# POWER_SUPPLY.net
KiCad netlist of a schematic drawn in Altium Designer
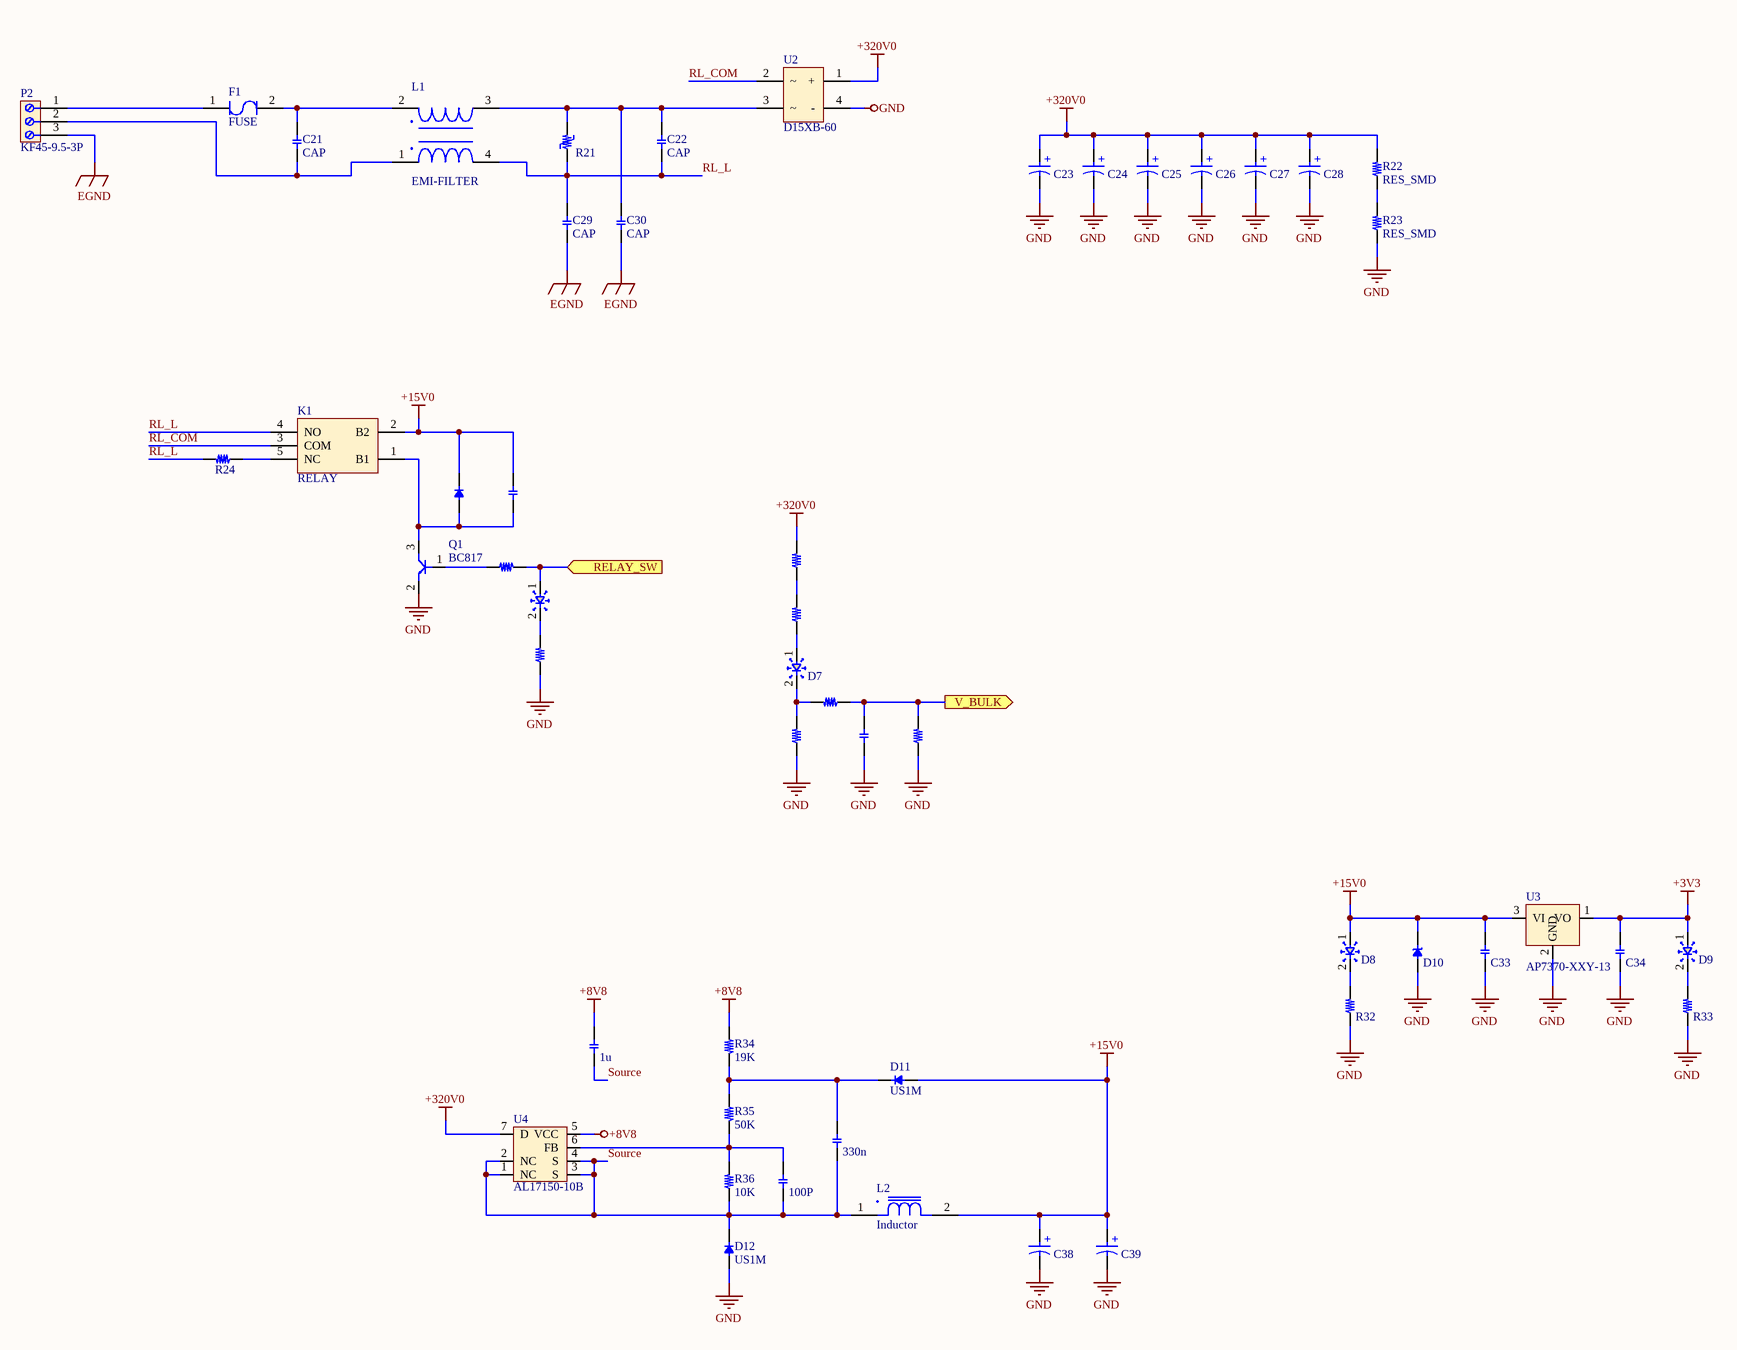
[diagram p0: POWER_SUPPLY.SchDoc]

(export (version "E")
  (design (tool "Eeschema 10.0.6"))
  (components
    (comp (ref "C21")
      (value "CAP")
      (footprint "C FILM 15mm")
      (libsource (lib "radmehr_library") (part "CAP"))
    )
    (comp (ref "C22")
      (value "CAP")
      (footprint "C FILM 15mm")
      (libsource (lib "radmehr_library") (part "CAP"))
    )
    (comp (ref "C23")
      (value "220µF")
      (footprint "WCAP-AIG8_D25H30")
      (description "WCAP-AIG8 Aluminum Electrolytic Capacitor, Snap-In, D25 x H30mm, 220µF, 400V")
      (fields
        (field (name "MANUFACTURER PART NUMBER") "861011384014")
        (field (name "MANUFACTURER") "Wurth Elektronik")
      )
      (libsource (lib "Altium_WCAP-AIG8 (rev22c)") (part "861011384014"))
    )
    (comp (ref "C24")
      (value "220µF")
      (footprint "WCAP-AIG8_D25H30")
      (description "WCAP-AIG8 Aluminum Electrolytic Capacitor, Snap-In, D25 x H30mm, 220µF, 400V")
      (fields
        (field (name "MANUFACTURER PART NUMBER") "861011384014")
        (field (name "MANUFACTURER") "Wurth Elektronik")
      )
      (libsource (lib "Altium_WCAP-AIG8 (rev22c)") (part "861011384014"))
    )
    (comp (ref "C25")
      (value "220µF")
      (footprint "WCAP-AIG8_D25H30")
      (description "WCAP-AIG8 Aluminum Electrolytic Capacitor, Snap-In, D25 x H30mm, 220µF, 400V")
      (fields
        (field (name "MANUFACTURER PART NUMBER") "861011384014")
        (field (name "MANUFACTURER") "Wurth Elektronik")
      )
      (libsource (lib "Altium_WCAP-AIG8 (rev22c)") (part "861011384014"))
    )
    (comp (ref "C26")
      (value "220µF")
      (footprint "WCAP-AIG8_D25H30")
      (description "WCAP-AIG8 Aluminum Electrolytic Capacitor, Snap-In, D25 x H30mm, 220µF, 400V")
      (fields
        (field (name "MANUFACTURER PART NUMBER") "861011384014")
        (field (name "MANUFACTURER") "Wurth Elektronik")
      )
      (libsource (lib "Altium_WCAP-AIG8 (rev22c)") (part "861011384014"))
    )
    (comp (ref "C27")
      (value "220µF")
      (footprint "WCAP-AIG8_D25H30")
      (description "WCAP-AIG8 Aluminum Electrolytic Capacitor, Snap-In, D25 x H30mm, 220µF, 400V")
      (fields
        (field (name "MANUFACTURER PART NUMBER") "861011384014")
        (field (name "MANUFACTURER") "Wurth Elektronik")
      )
      (libsource (lib "Altium_WCAP-AIG8 (rev22c)") (part "861011384014"))
    )
    (comp (ref "C28")
      (value "220µF")
      (footprint "WCAP-AIG8_D25H30")
      (description "WCAP-AIG8 Aluminum Electrolytic Capacitor, Snap-In, D25 x H30mm, 220µF, 400V")
      (fields
        (field (name "MANUFACTURER PART NUMBER") "861011384014")
        (field (name "MANUFACTURER") "Wurth Elektronik")
      )
      (libsource (lib "Altium_WCAP-AIG8 (rev22c)") (part "861011384014"))
    )
    (comp (ref "C29") (value "CAP") (footprint "CXY") (libsource (lib "radmehr_library") (part "CAP")))
    (comp (ref "C30") (value "CAP") (footprint "CXY") (libsource (lib "radmehr_library") (part "CAP")))
    (comp (ref "C31")
      (value "CAP_SMD")
      (footprint "C 0603")
      (libsource (lib "radmehr_library") (part "CAP_SMD"))
    )
    (comp (ref "C32")
      (value "CAP_SMD")
      (footprint "C 1206")
      (libsource (lib "radmehr_library") (part "CAP_SMD"))
    )
    (comp (ref "C33")
      (value "CAP_SMD")
      (footprint "C 0603")
      (libsource (lib "radmehr_library") (part "CAP_SMD"))
    )
    (comp (ref "C34")
      (value "CAP_SMD")
      (footprint "C 0603")
      (libsource (lib "radmehr_library") (part "CAP_SMD"))
    )
    (comp (ref "C35")
      (value "1u")
      (footprint "C 1206")
      (description "CAP_SMD")
      (libsource (lib "radmehr_library") (part "CAP_SMD"))
    )
    (comp (ref "C36")
      (value "330n")
      (footprint "C 1206")
      (description "CAP_SMD")
      (libsource (lib "radmehr_library") (part "CAP_SMD"))
    )
    (comp (ref "C37")
      (value "100P")
      (footprint "C 1206")
      (description "CAP_SMD")
      (libsource (lib "radmehr_library") (part "CAP_SMD"))
    )
    (comp (ref "C38")
      (value "220uF")
      (footprint "WCAP-ASLI_D10H10.5")
      (description "WCAP-ASLI Aluminum Electrolytic Capacitor, V-Chip, D10 x H10.5mm, 220uF, 50V")
      (fields
        (field (name "MANUFACTURER PART NUMBER") "865080657018")
        (field (name "MANUFACTURER") "Wurth Elektronik")
      )
      (libsource (lib "Altium_WCAP-ASLI (rev22d)") (part "865080657018"))
    )
    (comp (ref "C39")
      (value "220uF")
      (footprint "WCAP-ASLI_D10H10.5")
      (description "WCAP-ASLI Aluminum Electrolytic Capacitor, V-Chip, D10 x H10.5mm, 220uF, 50V")
      (fields
        (field (name "MANUFACTURER PART NUMBER") "865080657018")
        (field (name "MANUFACTURER") "Wurth Elektronik")
      )
      (libsource (lib "Altium_WCAP-ASLI (rev22d)") (part "865080657018"))
    )
    (comp (ref "D5")
      (value "DIOD_SMD")
      (footprint "D SOD-323")
      (libsource (lib "radmehr_library") (part "DIOD_SMD"))
    )
    (comp (ref "D6")
      (value "LED_SMD")
      (footprint "D 0603")
      (libsource (lib "radmehr_library") (part "LED_SMD"))
    )
    (comp (ref "D7")
      (value "LED_SMD")
      (footprint "D 1206")
      (libsource (lib "radmehr_library") (part "LED_SMD"))
    )
    (comp (ref "D8")
      (value "LED_SMD")
      (footprint "D 0603")
      (libsource (lib "radmehr_library") (part "LED_SMD"))
    )
    (comp (ref "D9")
      (value "LED_SMD")
      (footprint "D 0603")
      (libsource (lib "radmehr_library") (part "LED_SMD"))
    )
    (comp (ref "D10")
      (value "TVS_UI")
      (footprint "D SOD-123")
      (libsource (lib "radmehr_library") (part "DIOD_SMD_TVS_UI"))
    )
    (comp (ref "D11")
      (value "US1M")
      (footprint "DIOD_SMA")
      (description "DIOD_SMD")
      (libsource (lib "radmehr_library") (part "DIOD_SMD"))
    )
    (comp (ref "D12")
      (value "US1M")
      (footprint "DIOD_SMA")
      (description "DIOD_SMD")
      (libsource (lib "radmehr_library") (part "DIOD_SMD"))
    )
    (comp (ref "F1") (value "FUSE") (footprint "FUSE 1") (libsource (lib "radmehr_library") (part "FUSE")))
    (comp (ref "K1") (value "RELAY") (footprint "ALQ124") (libsource (lib "radmehr_library") (part "RELAY")))
    (comp (ref "L1")
      (value "EMI-FILTER")
      (footprint "EMI-FILTER-10*13")
      (libsource (lib "radmehr_library") (part "EMI-FILTER"))
    )
    (comp (ref "L2")
      (value "Inductor")
      (footprint "L_10*10_SMD")
      (libsource (lib "radmehr_library") (part "Inductor"))
    )
    (comp (ref "P2")
      (value "KF45-9.5-3P")
      (footprint "DG45C-B-03P-13")
      (libsource (lib "TERMINAL") (part "KF45-9.5-3P"))
    )
    (comp (ref "Q1")
      (value "BC817")
      (footprint "SOT-23_3_Q")
      (libsource (lib "radmehr_library") (part "BC817"))
    )
    (comp (ref "R21")
      (value "VARISTOR")
      (footprint "RTD")
      (libsource (lib "radmehr_library") (part "VARISTOR"))
    )
    (comp (ref "R22")
      (value "RES_SMD")
      (footprint "R 2512")
      (libsource (lib "radmehr_library") (part "RES_SMD"))
    )
    (comp (ref "R23")
      (value "RES_SMD")
      (footprint "R 2512")
      (libsource (lib "radmehr_library") (part "RES_SMD"))
    )
    (comp (ref "R24")
      (value "RES_THD")
      (footprint "R 5W VER")
      (libsource (lib "radmehr_library") (part "RES_THD"))
    )
    (comp (ref "R25")
      (value "RES_SMD")
      (footprint "R 1206")
      (libsource (lib "radmehr_library") (part "RES_SMD"))
    )
    (comp (ref "R26")
      (value "RES_SMD")
      (footprint "R 0603")
      (libsource (lib "radmehr_library") (part "RES_SMD"))
    )
    (comp (ref "R27")
      (value "RES_SMD")
      (footprint "R 1206")
      (libsource (lib "radmehr_library") (part "RES_SMD"))
    )
    (comp (ref "R28")
      (value "RES_SMD")
      (footprint "R 0603")
      (libsource (lib "radmehr_library") (part "RES_SMD"))
    )
    (comp (ref "R29")
      (value "RES_SMD")
      (footprint "R 1206")
      (libsource (lib "radmehr_library") (part "RES_SMD"))
    )
    (comp (ref "R30")
      (value "RES_SMD")
      (footprint "R 1206")
      (libsource (lib "radmehr_library") (part "RES_SMD"))
    )
    (comp (ref "R31")
      (value "RES_SMD")
      (footprint "R 0603")
      (libsource (lib "radmehr_library") (part "RES_SMD"))
    )
    (comp (ref "R32")
      (value "RES_SMD")
      (footprint "R 0603")
      (libsource (lib "radmehr_library") (part "RES_SMD"))
    )
    (comp (ref "R33")
      (value "RES_SMD")
      (footprint "R 0603")
      (libsource (lib "radmehr_library") (part "RES_SMD"))
    )
    (comp (ref "R34")
      (value "19K")
      (footprint "R 1206")
      (description "RES_SMD")
      (libsource (lib "radmehr_library") (part "RES_SMD"))
    )
    (comp (ref "R35")
      (value "50K")
      (footprint "R 1206")
      (description "RES_SMD")
      (libsource (lib "radmehr_library") (part "RES_SMD"))
    )
    (comp (ref "R36")
      (value "10K")
      (footprint "R 1206")
      (description "RES_SMD")
      (libsource (lib "radmehr_library") (part "RES_SMD"))
    )
    (comp (ref "U2")
      (value "D15XB-60")
      (footprint "D15XB-60")
      (libsource (lib "radmehr_library") (part "D15XB-60"))
    )
    (comp (ref "U3")
      (value "AP7370-XXY-13")
      (footprint "SOT89-U")
      (libsource (lib "radmehr_library") (part "AP7370-XXY-13"))
    )
    (comp (ref "U4")
      (value "AL17150-10B")
      (footprint "SOIC-7")
      (libsource (lib "radmehr_library") (part "AL17150-10B"))
    )
  )
  (nets
    (net (code "1") (name "+3V3") (class "Default")
      (node (ref "C34") (pin "2") (pinfunction "2_2") (pintype "passive"))
      (node (ref "D9") (pin "1") (pintype "passive"))
      (node (ref "U3") (pin "1") (pinfunction "VO_1") (pintype "passive"))
    )
    (net (code "2") (name "+8V8") (class "Default")
      (node (ref "C35") (pin "2") (pinfunction "2_2") (pintype "passive"))
      (node (ref "R34") (pin "1") (pinfunction "1_1") (pintype "passive"))
      (node (ref "U4") (pin "5") (pinfunction "VCC_5") (pintype "passive"))
    )
    (net (code "3") (name "+15V0") (class "Default")
      (node (ref "C31") (pin "2") (pinfunction "2_2") (pintype "passive"))
      (node (ref "C33") (pin "2") (pinfunction "2_2") (pintype "passive"))
      (node (ref "C38") (pin "1") (pinfunction "P_1") (pintype "passive"))
      (node (ref "C39") (pin "1") (pinfunction "P_1") (pintype "passive"))
      (node (ref "D10") (pin "2") (pinfunction "2_2") (pintype "passive"))
      (node (ref "D11") (pin "1") (pinfunction "1_1") (pintype "passive"))
      (node (ref "D5") (pin "2") (pinfunction "2_2") (pintype "passive"))
      (node (ref "D8") (pin "1") (pintype "passive"))
      (node (ref "K1") (pin "2") (pinfunction "B2_2") (pintype "power_in"))
      (node (ref "L2") (pin "2") (pintype "passive"))
      (node (ref "U3") (pin "3") (pinfunction "VI_3") (pintype "passive"))
    )
    (net (code "4") (name "+320V0") (class "Default")
      (node (ref "C23") (pin "1") (pinfunction "P_1") (pintype "passive"))
      (node (ref "C24") (pin "1") (pinfunction "P_1") (pintype "passive"))
      (node (ref "C25") (pin "1") (pinfunction "P_1") (pintype "passive"))
      (node (ref "C26") (pin "1") (pinfunction "P_1") (pintype "passive"))
      (node (ref "C27") (pin "1") (pinfunction "P_1") (pintype "passive"))
      (node (ref "C28") (pin "1") (pinfunction "P_1") (pintype "passive"))
      (node (ref "R22") (pin "2") (pinfunction "2_2") (pintype "passive"))
      (node (ref "R25") (pin "2") (pinfunction "2_2") (pintype "passive"))
      (node (ref "U2") (pin "1") (pinfunction "+_1") (pintype "passive"))
      (node (ref "U4") (pin "7") (pinfunction "D_7") (pintype "passive"))
    )
    (net (code "5") (name "/RELAY_SW") (class "Default")
      (node (ref "D6") (pin "1") (pintype "passive"))
      (node (ref "R26") (pin "2") (pinfunction "2_2") (pintype "passive"))
    )
    (net (code "6") (name "/RL_COM") (class "Default")
      (node (ref "K1") (pin "3") (pinfunction "COM_3") (pintype "power_in"))
      (node (ref "U2") (pin "2") (pinfunction "~_2") (pintype "passive"))
    )
    (net (code "7") (name "/RL_L") (class "Default")
      (node (ref "C22") (pin "1") (pinfunction "1_1") (pintype "passive"))
      (node (ref "C29") (pin "2") (pinfunction "2_2") (pintype "passive"))
      (node (ref "K1") (pin "4") (pinfunction "NO_4") (pintype "power_in"))
      (node (ref "L1") (pin "4") (pinfunction "4_4") (pintype "power_in"))
      (node (ref "R21") (pin "1") (pinfunction "1_1") (pintype "passive"))
      (node (ref "R24") (pin "2") (pinfunction "2_2") (pintype "passive"))
    )
    (net (code "8") (name "/Source") (class "Default")
      (node (ref "C35") (pin "1") (pinfunction "1_1") (pintype "passive"))
      (node (ref "C36") (pin "1") (pinfunction "1_1") (pintype "passive"))
      (node (ref "C37") (pin "1") (pinfunction "1_1") (pintype "passive"))
      (node (ref "D12") (pin "2") (pinfunction "2_2") (pintype "passive"))
      (node (ref "L2") (pin "1") (pintype "passive"))
      (node (ref "R36") (pin "1") (pinfunction "1_1") (pintype "passive"))
      (node (ref "U4") (pin "1") (pinfunction "NC_1") (pintype "passive"))
      (node (ref "U4") (pin "2") (pinfunction "NC_2") (pintype "passive"))
      (node (ref "U4") (pin "3") (pinfunction "S_3") (pintype "passive"))
      (node (ref "U4") (pin "4") (pinfunction "S_4") (pintype "passive"))
    )
    (net (code "9") (name "/V_BULK") (class "Default")
      (node (ref "C32") (pin "2") (pinfunction "2_2") (pintype "passive"))
      (node (ref "R29") (pin "1") (pinfunction "1_1") (pintype "passive"))
      (node (ref "R31") (pin "2") (pinfunction "2_2") (pintype "passive"))
    )
    (net (code "10") (name "EGND") (class "Default")
      (node (ref "C29") (pin "1") (pinfunction "1_1") (pintype "passive"))
      (node (ref "C30") (pin "1") (pinfunction "1_1") (pintype "passive"))
      (node (ref "P2") (pin "3") (pinfunction "3_3") (pintype "passive"))
    )
    (net (code "11") (name "GND") (class "Default")
      (node (ref "C23") (pin "2") (pinfunction "N_2") (pintype "passive"))
      (node (ref "C24") (pin "2") (pinfunction "N_2") (pintype "passive"))
      (node (ref "C25") (pin "2") (pinfunction "N_2") (pintype "passive"))
      (node (ref "C26") (pin "2") (pinfunction "N_2") (pintype "passive"))
      (node (ref "C27") (pin "2") (pinfunction "N_2") (pintype "passive"))
      (node (ref "C28") (pin "2") (pinfunction "N_2") (pintype "passive"))
      (node (ref "C32") (pin "1") (pinfunction "1_1") (pintype "passive"))
      (node (ref "C33") (pin "1") (pinfunction "1_1") (pintype "passive"))
      (node (ref "C34") (pin "1") (pinfunction "1_1") (pintype "passive"))
      (node (ref "C38") (pin "2") (pinfunction "N_2") (pintype "passive"))
      (node (ref "C39") (pin "2") (pinfunction "N_2") (pintype "passive"))
      (node (ref "D10") (pin "1") (pinfunction "1_1") (pintype "passive"))
      (node (ref "D12") (pin "1") (pinfunction "1_1") (pintype "passive"))
      (node (ref "Q1") (pin "2") (pinfunction "E_2") (pintype "passive"))
      (node (ref "R23") (pin "1") (pinfunction "1_1") (pintype "passive"))
      (node (ref "R28") (pin "1") (pinfunction "1_1") (pintype "passive"))
      (node (ref "R30") (pin "1") (pinfunction "1_1") (pintype "passive"))
      (node (ref "R31") (pin "1") (pinfunction "1_1") (pintype "passive"))
      (node (ref "R32") (pin "1") (pinfunction "1_1") (pintype "passive"))
      (node (ref "R33") (pin "1") (pinfunction "1_1") (pintype "passive"))
      (node (ref "U2") (pin "4") (pinfunction "-_4") (pintype "passive"))
      (node (ref "U3") (pin "2") (pinfunction "GND_2") (pintype "passive"))
    )
    (net (code "12") (name "Net-(C21-Pad1)") (class "Default")
      (node (ref "C21") (pin "1") (pinfunction "1_1") (pintype "passive"))
      (node (ref "L1") (pin "1") (pinfunction "1_1") (pintype "power_in"))
      (node (ref "P2") (pin "2") (pinfunction "2_2") (pintype "passive"))
    )
    (net (code "13") (name "Net-(C21-Pad2)") (class "Default")
      (node (ref "C21") (pin "2") (pinfunction "2_2") (pintype "passive"))
      (node (ref "F1") (pin "2") (pintype "passive"))
      (node (ref "L1") (pin "2") (pinfunction "2_2") (pintype "power_in"))
    )
    (net (code "14") (name "Net-(C22-Pad2)") (class "Default")
      (node (ref "C22") (pin "2") (pinfunction "2_2") (pintype "passive"))
      (node (ref "C30") (pin "2") (pinfunction "2_2") (pintype "passive"))
      (node (ref "L1") (pin "3") (pinfunction "3_3") (pintype "power_in"))
      (node (ref "R21") (pin "2") (pinfunction "2_2") (pintype "passive"))
      (node (ref "U2") (pin "3") (pinfunction "~_3") (pintype "passive"))
    )
    (net (code "15") (name "Net-(C36-Pad2)") (class "Default")
      (node (ref "C36") (pin "2") (pinfunction "2_2") (pintype "passive"))
      (node (ref "D11") (pin "2") (pinfunction "2_2") (pintype "passive"))
      (node (ref "R34") (pin "2") (pinfunction "2_2") (pintype "passive"))
      (node (ref "R35") (pin "1") (pinfunction "1_1") (pintype "passive"))
    )
    (net (code "16") (name "Net-(D6-Pad2)") (class "Default")
      (node (ref "D6") (pin "2") (pintype "passive"))
      (node (ref "R28") (pin "2") (pinfunction "2_2") (pintype "passive"))
    )
    (net (code "17") (name "Net-(D7-Pad1)") (class "Default")
      (node (ref "D7") (pin "1") (pintype "passive"))
      (node (ref "R27") (pin "1") (pinfunction "1_1") (pintype "passive"))
    )
    (net (code "18") (name "Net-(D7-Pad2)") (class "Default")
      (node (ref "D7") (pin "2") (pintype "passive"))
      (node (ref "R29") (pin "2") (pinfunction "2_2") (pintype "passive"))
      (node (ref "R30") (pin "2") (pinfunction "2_2") (pintype "passive"))
    )
    (net (code "19") (name "Net-(D8-Pad2)") (class "Default")
      (node (ref "D8") (pin "2") (pintype "passive"))
      (node (ref "R32") (pin "2") (pinfunction "2_2") (pintype "passive"))
    )
    (net (code "20") (name "Net-(D9-Pad2)") (class "Default")
      (node (ref "D9") (pin "2") (pintype "passive"))
      (node (ref "R33") (pin "2") (pinfunction "2_2") (pintype "passive"))
    )
    (net (code "21") (name "Net-(F1-Pad1)") (class "Default")
      (node (ref "F1") (pin "1") (pintype "passive"))
      (node (ref "P2") (pin "1") (pinfunction "1_1") (pintype "passive"))
    )
    (net (code "22") (name "Net-(K1-B1)") (class "Default")
      (node (ref "C31") (pin "1") (pinfunction "1_1") (pintype "passive"))
      (node (ref "D5") (pin "1") (pinfunction "1_1") (pintype "passive"))
      (node (ref "K1") (pin "1") (pinfunction "B1_1") (pintype "power_in"))
      (node (ref "Q1") (pin "3") (pinfunction "C_3") (pintype "passive"))
    )
    (net (code "23") (name "Net-(K1-NC)") (class "Default")
      (node (ref "K1") (pin "5") (pinfunction "NC_5") (pintype "power_in"))
      (node (ref "R24") (pin "1") (pinfunction "1_1") (pintype "passive"))
    )
    (net (code "24") (name "Net-(Q1-B)") (class "Default")
      (node (ref "Q1") (pin "1") (pinfunction "B_1") (pintype "passive"))
      (node (ref "R26") (pin "1") (pinfunction "1_1") (pintype "passive"))
    )
    (net (code "25") (name "Net-(R22-Pad1)") (class "Default")
      (node (ref "R22") (pin "1") (pinfunction "1_1") (pintype "passive"))
      (node (ref "R23") (pin "2") (pinfunction "2_2") (pintype "passive"))
    )
    (net (code "26") (name "Net-(R25-Pad1)") (class "Default")
      (node (ref "R25") (pin "1") (pinfunction "1_1") (pintype "passive"))
      (node (ref "R27") (pin "2") (pinfunction "2_2") (pintype "passive"))
    )
    (net (code "27") (name "Net-(U4-FB)") (class "Default")
      (node (ref "C37") (pin "2") (pinfunction "2_2") (pintype "passive"))
      (node (ref "R35") (pin "2") (pinfunction "2_2") (pintype "passive"))
      (node (ref "R36") (pin "2") (pinfunction "2_2") (pintype "passive"))
      (node (ref "U4") (pin "6") (pinfunction "FB_6") (pintype "passive"))
    )
  )
)
